# STM32G0B1CEU6.net
KiCad netlist of a schematic drawn in Altium Designer
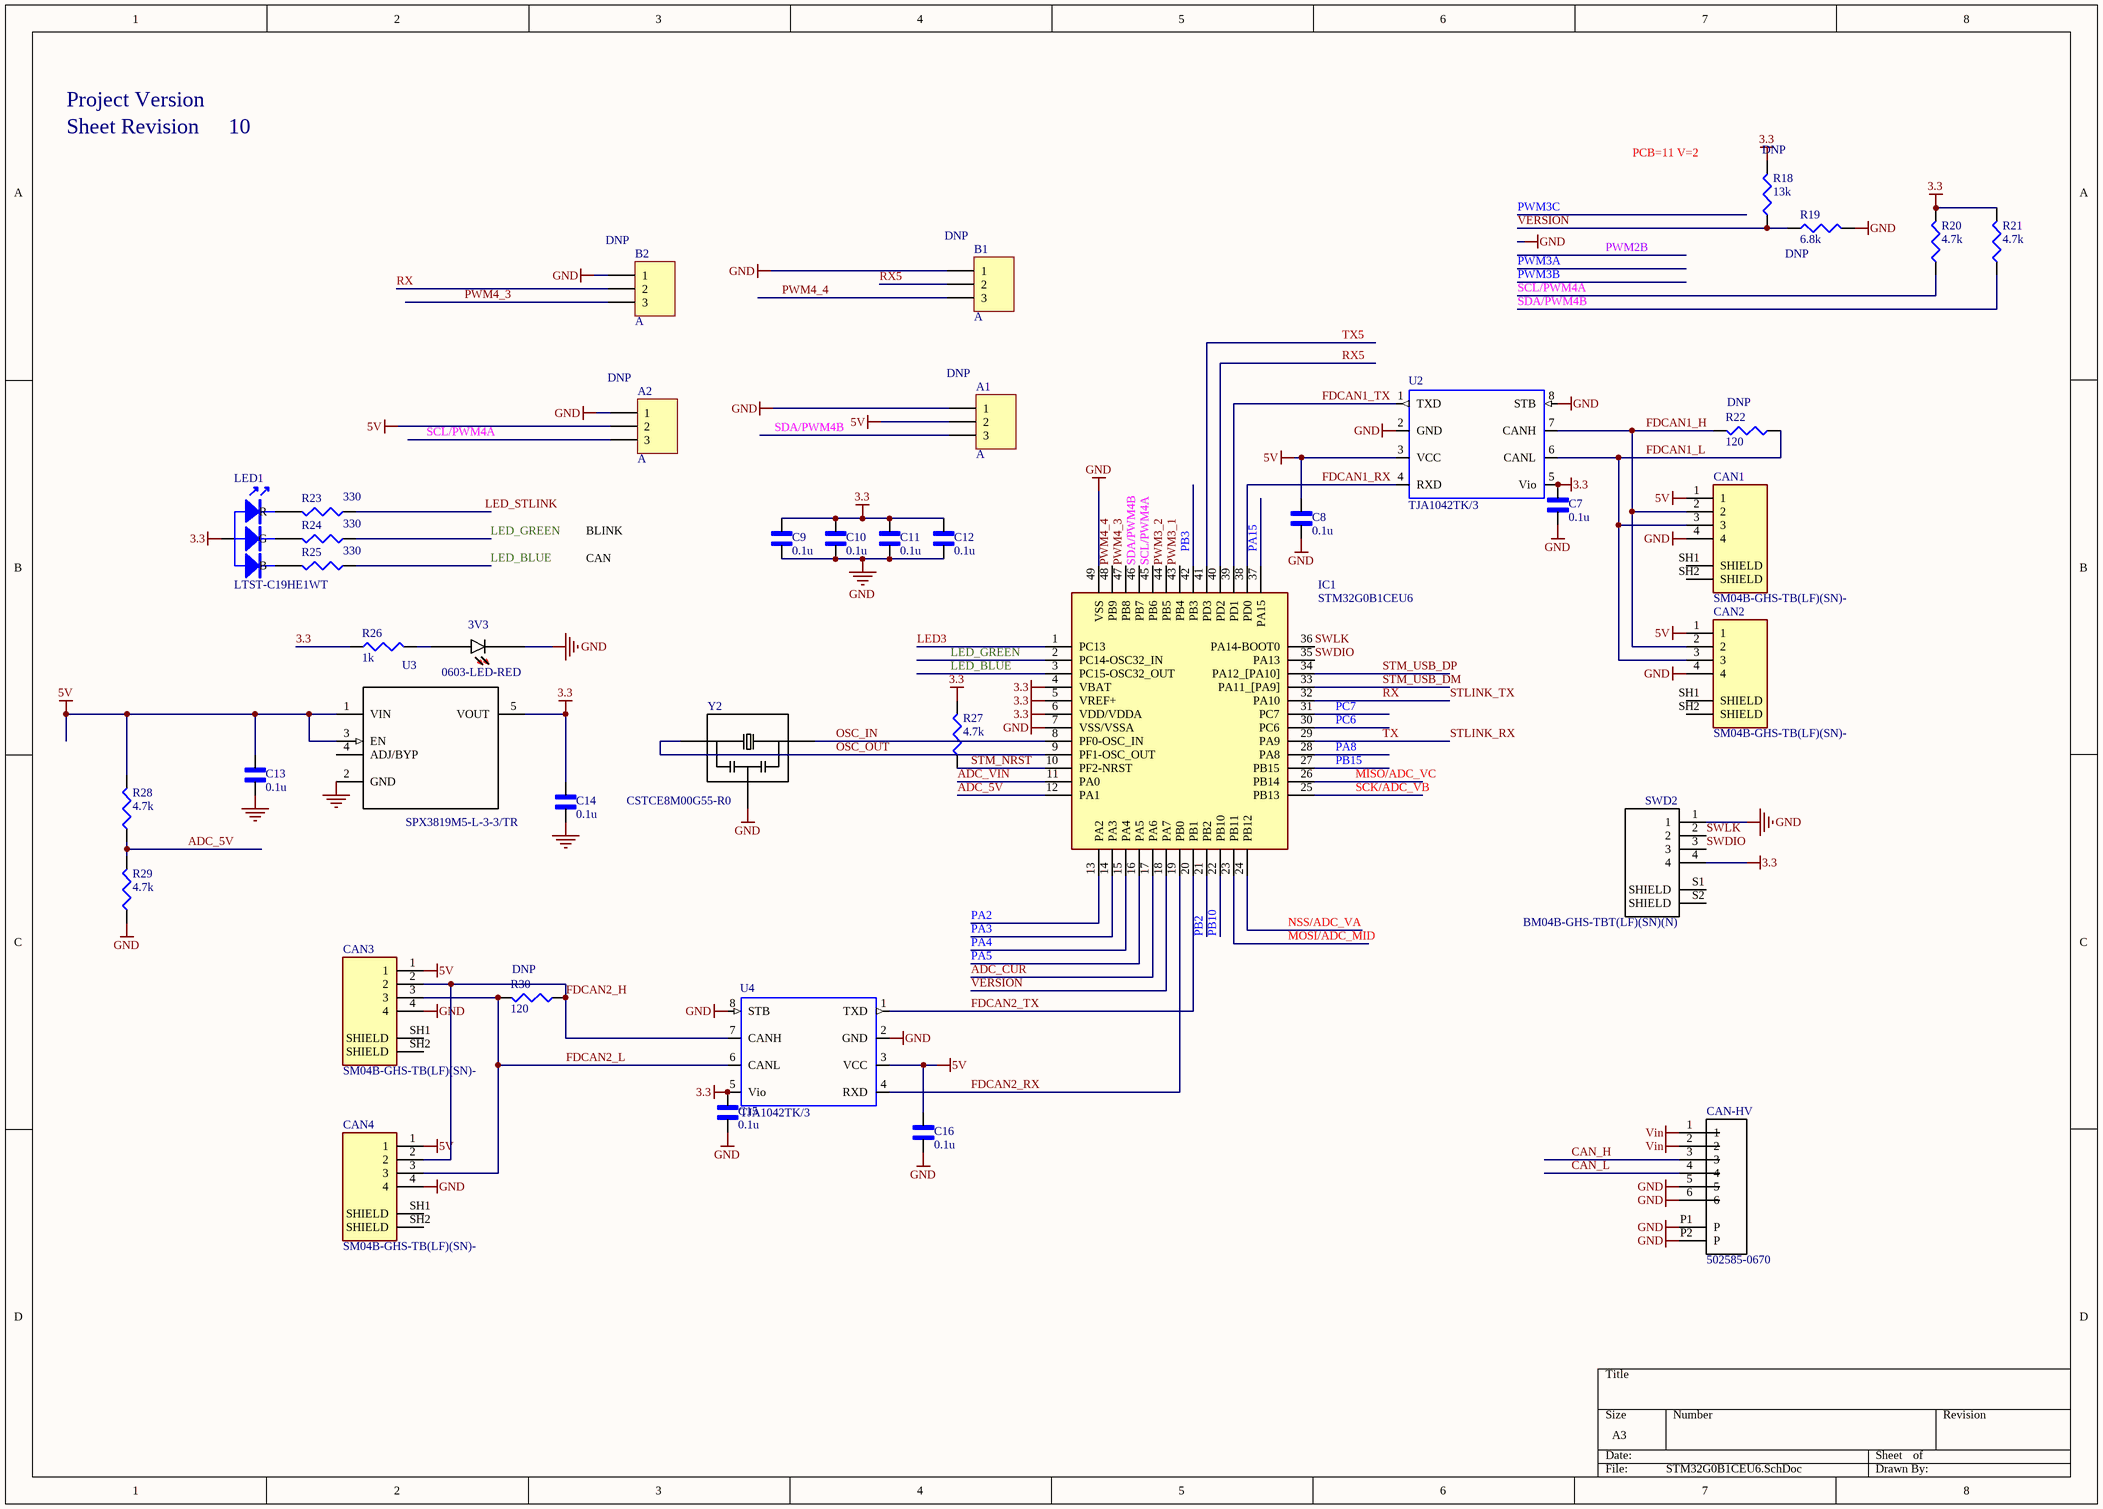
[diagram p0: STM32G0B1CEU6.SchDoc]

(export (version "E")
  (design (tool "Eeschema 10.0.6"))
  (components
    (comp (ref "3V3")
      (value "0603-LED-RED")
      (footprint "*LEDM1608X80_LTE-C1906R-14(Primary)")
      (description "Red 620nm LED Indication - Discrete 2.2V 0603 (1608 Metric)")
      (fields (field (name "MP") "LTST-C194KRKT"))
      (libsource (lib "lib") (part "0603-LED-RED"))
    )
    (comp (ref "A1")
      (value "A")
      (footprint "HDR Side 3 pin")
      (description "Header, 3-Pin")
      (fields
        (field (name "INSTRUCTIONS") "DNP")
        (field (name "MF") "Connfly electronic (Zhenqin)")
        (field (name "MP") "PLS-3 (DS1021-1x3)")
      )
      (libsource (lib "DC_DC") (part "Header 3"))
    )
    (comp (ref "A2")
      (value "A")
      (footprint "HDR Side 3 pin")
      (description "Header, 3-Pin")
      (fields
        (field (name "INSTRUCTIONS") "DNP")
        (field (name "MF") "Connfly electronic (Zhenqin)")
        (field (name "MP") "PLS-3 (DS1021-1x3)")
      )
      (libsource (lib "DC_DC") (part "Header 3"))
    )
    (comp (ref "B1")
      (value "A")
      (footprint "HDR Side 3 pin")
      (description "Header, 3-Pin")
      (fields
        (field (name "INSTRUCTIONS") "DNP")
        (field (name "MF") "Connfly electronic (Zhenqin)")
        (field (name "MP") "PLS-3 (DS1021-1x3)")
      )
      (libsource (lib "DC_DC") (part "Header 3"))
    )
    (comp (ref "B2")
      (value "A")
      (footprint "HDR Side 3 pin")
      (description "Header, 3-Pin")
      (fields
        (field (name "INSTRUCTIONS") "DNP")
        (field (name "MF") "Connfly electronic (Zhenqin)")
        (field (name "MP") "PLS-3 (DS1021-1x3)")
      )
      (libsource (lib "DC_DC") (part "Header 3"))
    )
    (comp (ref "C7")
      (value "0.1u")
      (footprint "CAPC1005X55N")
      (description "GCM155R71H104KE02D, Чип 0402 X7R 0.1uF +10% 50V,Конденсатор")
      (fields (field (name "MF") "Murata") (field (name "MP") "GCM155R71H104KE02D"))
      (libsource (lib "lib") (part "GCM155R71H104KE02D"))
    )
    (comp (ref "C8")
      (value "0.1u")
      (footprint "CAPC1005X55N")
      (description "GCM155R71H104KE02D, Чип 0402 X7R 0.1uF +10% 50V,Конденсатор")
      (fields (field (name "MF") "Murata") (field (name "MP") "GCM155R71H104KE02D"))
      (libsource (lib "lib") (part "GCM155R71H104KE02D"))
    )
    (comp (ref "C9")
      (value "0.1u")
      (footprint "CAPC1005X55N")
      (description "GCM155R71H104KE02D, Чип 0402 X7R 0.1uF +10% 50V,Конденсатор")
      (fields (field (name "MF") "Murata") (field (name "MP") "GCM155R71H104KE02D"))
      (libsource (lib "lib") (part "GCM155R71H104KE02D"))
    )
    (comp (ref "C10")
      (value "0.1u")
      (footprint "CAPC1005X55N")
      (description "GCM155R71H104KE02D, Чип 0402 X7R 0.1uF +10% 50V,Конденсатор")
      (fields (field (name "MF") "Murata") (field (name "MP") "GCM155R71H104KE02D"))
      (libsource (lib "lib") (part "GCM155R71H104KE02D"))
    )
    (comp (ref "C11")
      (value "0.1u")
      (footprint "CAPC1005X55N")
      (description "GCM155R71H104KE02D, Чип 0402 X7R 0.1uF +10% 50V,Конденсатор")
      (fields (field (name "MF") "Murata") (field (name "MP") "GCM155R71H104KE02D"))
      (libsource (lib "lib") (part "GCM155R71H104KE02D"))
    )
    (comp (ref "C12")
      (value "0.1u")
      (footprint "CAPC1005X55N")
      (description "GCM155R71H104KE02D, Чип 0402 X7R 0.1uF +10% 50V,Конденсатор")
      (fields (field (name "MF") "Murata") (field (name "MP") "GCM155R71H104KE02D"))
      (libsource (lib "lib") (part "GCM155R71H104KE02D"))
    )
    (comp (ref "C13")
      (value "0.1u")
      (footprint "CAPC1005X55N")
      (description "GCM155R71H104KE02D, Чип 0402 X7R 0.1uF +10% 50V,Конденсатор")
      (fields (field (name "MF") "Murata") (field (name "MP") "GCM155R71H104KE02D"))
      (libsource (lib "lib") (part "GCM155R71H104KE02D"))
    )
    (comp (ref "C14")
      (value "0.1u")
      (footprint "CAPC1005X55N")
      (description "GCM155R71H104KE02D, Чип 0402 X7R 0.1uF +10% 50V,Конденсатор")
      (fields (field (name "MF") "Murata") (field (name "MP") "GCM155R71H104KE02D"))
      (libsource (lib "lib") (part "GCM155R71H104KE02D"))
    )
    (comp (ref "C15")
      (value "0.1u")
      (footprint "CAPC1005X55N")
      (description "GCM155R71H104KE02D, Чип 0402 X7R 0.1uF +10% 50V,Конденсатор")
      (fields (field (name "MF") "Murata") (field (name "MP") "GCM155R71H104KE02D"))
      (libsource (lib "lib") (part "GCM155R71H104KE02D"))
    )
    (comp (ref "C16")
      (value "0.1u")
      (footprint "CAPC1005X55N")
      (description "GCM155R71H104KE02D, Чип 0402 X7R 0.1uF +10% 50V,Конденсатор")
      (fields (field (name "MF") "Murata") (field (name "MP") "GCM155R71H104KE02D"))
      (libsource (lib "lib") (part "GCM155R71H104KE02D"))
    )
    (comp (ref "CAN-HV")
      (value "502585-0670")
      (footprint "MOLEX_502585-0670")
      (fields (field (name "MF") "Molex"))
      (libsource (lib "lib") (part "502585-0670"))
    )
    (comp (ref "CAN1")
      (value "SM04B-GHS-TB(LF)(SN)-")
      (footprint "JST_SM04B-GHS-TB(LF)(SN)-")
      (description "Connector Header Surface Mount, Right Angle 4 position 0.049 _1.25mm_")
      (fields (field (name "MP") "SM04B-GHS-TB(LF)(SN)") (field (name "MF") "JST Sales"))
      (libsource (lib "") (part "SM04B-GHS-TB(LF)(SN)-_1"))
    )
    (comp (ref "CAN2")
      (value "SM04B-GHS-TB(LF)(SN)-")
      (footprint "JST_SM04B-GHS-TB(LF)(SN)-")
      (description "Connector Header Surface Mount, Right Angle 4 position 0.049 _1.25mm_")
      (fields (field (name "MP") "SM04B-GHS-TB(LF)(SN)") (field (name "MF") "JST Sales"))
      (libsource (lib "") (part "SM04B-GHS-TB(LF)(SN)-_1"))
    )
    (comp (ref "CAN3")
      (value "SM04B-GHS-TB(LF)(SN)-")
      (footprint "JST_SM04B-GHS-TB(LF)(SN)-")
      (description "Connector Header Surface Mount, Right Angle 4 position 0.049 _1.25mm_")
      (fields (field (name "MP") "SM04B-GHS-TB(LF)(SN)") (field (name "MF") "JST Sales"))
      (libsource (lib "lib") (part "SM04B-GHS-TB(LF)(SN)-"))
    )
    (comp (ref "CAN4")
      (value "SM04B-GHS-TB(LF)(SN)-")
      (footprint "JST_SM04B-GHS-TB(LF)(SN)-")
      (description "Connector Header Surface Mount, Right Angle 4 position 0.049 _1.25mm_")
      (fields (field (name "MP") "SM04B-GHS-TB(LF)(SN)") (field (name "MF") "JST Sales"))
      (libsource (lib "lib") (part "SM04B-GHS-TB(LF)(SN)-"))
    )
    (comp (ref "IC1")
      (value "STM32G0B1CEU6")
      (footprint "QFN50P700X700X60-49N-D")
      (description "Integrated Circuit")
      (fields
        (field (name "MF") "STMicroelectronics")
        (field (name "MOUSER PART NUMBER") "511-STM32G0B1CEU6")
      )
      (libsource (lib "lib") (part "STM32G0B1CxU6"))
    )
    (comp (ref "LED1")
      (value "LTST-C19HE1WT")
      (footprint "LTST-C19HE1WT")
      (description "Blue/Green/Red")
      (libsource (lib "lib") (part "RGB_LED_5MM"))
    )
    (comp (ref "R18")
      (value "13k")
      (footprint "RESC1005X40N")
      (description "0.062Вт 0402 13 кОм, 1%, Чип резистор (SMD)")
      (fields
        (field (name "INSTRUCTIONS") "DNP")
        (field (name "MF") "Yageo or NXP")
        (field (name "MP") "RC0402FR-0713KL")
      )
      (libsource (lib "lib") (part "RC0402FR-0713KL"))
    )
    (comp (ref "R19")
      (value "6.8k")
      (footprint "RESC1005X40N")
      (description "0.062Вт 0402 6.8 кОм, 1%, Чип резистор (SMD)")
      (fields
        (field (name "INSTRUCTIONS") "DNP")
        (field (name "MF") "Yageo or NXP")
        (field (name "MP") "RC0402FR-076K8L")
      )
      (libsource (lib "lib") (part "RC0402FR-076K8L"))
    )
    (comp (ref "R20")
      (value "4.7k")
      (footprint "RESC1005X40N")
      (description "0.062Вт 0402 4.7 кОм, 1%, Чип резистор (SMD)")
      (fields (field (name "MF") "Yageo or NXP") (field (name "MP") "RC0402FR-074K7L"))
      (libsource (lib "lib") (part "RC0402FR-074K7L"))
    )
    (comp (ref "R21")
      (value "4.7k")
      (footprint "RESC1005X40N")
      (description "0.062Вт 0402 4.7 кОм, 1%, Чип резистор (SMD)")
      (fields (field (name "MF") "Yageo or NXP") (field (name "MP") "RC0402FR-074K7L"))
      (libsource (lib "lib") (part "RC0402FR-074K7L"))
    )
    (comp (ref "R22")
      (value "120")
      (footprint "J1-0603")
      (description "120 Ohms 1 0.1 W 1 10 W Chip Resistor 0603 1608 Metric Thick Film")
      (fields
        (field (name "INSTRUCTIONS") "DNP")
        (field (name "MP") "RC0603FR-07120RL")
        (field (name "Comment") "Res3")
      )
      (libsource (lib "Miscellaneous Devices") (part "Res3"))
    )
    (comp (ref "R23")
      (value "330")
      (footprint "RESC1005X40N")
      (description "0.062Вт 0402 330 Ом, 1%, Чип резистор (SMD)")
      (fields (field (name "MF") "Yageo or NXP") (field (name "MP") "RC0402FR-07330RL"))
      (libsource (lib "lib") (part "RC0402FR-07330RL"))
    )
    (comp (ref "R24")
      (value "330")
      (footprint "RESC1005X40N")
      (description "0.062Вт 0402 330 Ом, 1%, Чип резистор (SMD)")
      (fields (field (name "MF") "Yageo or NXP") (field (name "MP") "RC0402FR-07330RL"))
      (libsource (lib "lib") (part "RC0402FR-07330RL"))
    )
    (comp (ref "R25")
      (value "330")
      (footprint "RESC1005X40N")
      (description "0.062Вт 0402 330 Ом, 1%, Чип резистор (SMD)")
      (fields (field (name "MF") "Yageo or NXP") (field (name "MP") "RC0402FR-07330RL"))
      (libsource (lib "lib") (part "RC0402FR-07330RL"))
    )
    (comp (ref "R26")
      (value "1k")
      (footprint "RESC1005X40N")
      (description "0.062Вт 0402 1 кОм, 1%, Чип резистор (SMD)")
      (fields (field (name "MF") "Yageo or NXP") (field (name "MP") "RC0402FR-071KL"))
      (libsource (lib "lib") (part "RC0402FR-071KL"))
    )
    (comp (ref "R27")
      (value "4.7k")
      (footprint "RESC1005X40N")
      (description "0.062Вт 0402 4.7 кОм, 1%, Чип резистор (SMD)")
      (fields (field (name "MF") "Yageo or NXP") (field (name "MP") "RC0402FR-074K7L"))
      (libsource (lib "lib") (part "RC0402FR-074K7L"))
    )
    (comp (ref "R28")
      (value "4.7k")
      (footprint "RESC1005X40N")
      (description "0.062Вт 0402 4.7 кОм, 1%, Чип резистор (SMD)")
      (fields (field (name "MF") "Yageo or NXP") (field (name "MP") "RC0402FR-074K7L"))
      (libsource (lib "lib") (part "RC0402FR-074K7L"))
    )
    (comp (ref "R29")
      (value "4.7k")
      (footprint "RESC1005X40N")
      (description "0.062Вт 0402 4.7 кОм, 1%, Чип резистор (SMD)")
      (fields (field (name "MF") "Yageo or NXP") (field (name "MP") "RC0402FR-074K7L"))
      (libsource (lib "lib") (part "RC0402FR-074K7L"))
    )
    (comp (ref "R30")
      (value "120")
      (footprint "J1-0603")
      (description "120 Ohms 1 0.1 W 1 10 W Chip Resistor 0603 1608 Metric Thick Film")
      (fields
        (field (name "INSTRUCTIONS") "DNP")
        (field (name "MP") "RC0603FR-07120RL")
        (field (name "Comment") "Res3")
      )
      (libsource (lib "Miscellaneous Devices") (part "Res3"))
    )
    (comp (ref "SWD2")
      (value "BM04B-GHS-TBT(LF)(SN)(N)")
      (footprint "JST_BM04B-GHS-holes")
      (description "Conn Shrouded Header HDR 4 POS 1.25mm Solder ST SMD Reel")
      (fields (field (name "MF") "JST Sales") (field (name "MP") "SM04B-GHS-TB(LF)(SN)"))
      (libsource (lib "lib") (part "BM04B-GHS-TBT(LF)(SN)(N)"))
    )
    (comp (ref "U2")
      (value "TJA1042TK/3")
      (footprint "SOT782-1")
      (description "1/1 Transceiver Half CANbus 8-SO")
      (fields (field (name "MF") "NXP USA"))
      (libsource (lib "lib") (part "TJA1042TK/3"))
    )
    (comp (ref "U3")
      (value "SPX3819M5-L-3-3/TR")
      (footprint "*SOT95P280X145-5N")
      (description "Low Dropout Voltage Regulator, Adjustable 0.5A, В±1%, 2.5 to 16 Vin, 5-Pin SOT-23")
      (fields (field (name "MF") "MaxLinear, Inc."))
      (libsource (lib "DC_DC") (part "SPX3819M5-L"))
    )
    (comp (ref "U4")
      (value "TJA1042TK/3")
      (footprint "SOT782-1")
      (description "1/1 Transceiver Half CANbus 8-SO")
      (fields (field (name "MF") "NXP USA"))
      (libsource (lib "lib") (part "TJA1042TK/3"))
    )
    (comp (ref "Y2")
      (value "CSTCE8M00G55-R0")
      (footprint "*OSC_CSTCE8M00G55-R0")
      (description "Ceramic Resonator 8MHz ??0.5% _Tol_ ??0.2% _Stability_ 33pF 40Ohm 3-Pin CSMD T/R")
      (fields (field (name "MP") "CSTCE8M00G55-R0 or CSTCE8M00G52-R0") (field (name "MF") "Murata"))
      (libsource (lib "lib") (part "CSTCE8M00G55-R0"))
    )
  )
  (nets
    (net (code "1") (name "/ADC_5V") (class "Default")
      (node (ref "IC1") (pin "12") (pinfunction "PA1_12") (pintype "passive"))
      (node (ref "R28") (pin "1") (pinfunction "1_1") (pintype "passive"))
      (node (ref "R29") (pin "2") (pinfunction "2_2") (pintype "passive"))
    )
    (net (code "2") (name "/ADC_CUR") (class "Default")
      (node (ref "IC1") (pin "17") (pinfunction "PA6_17") (pintype "passive"))
    )
    (net (code "3") (name "/ADC_VIN") (class "Default")
      (node (ref "IC1") (pin "11") (pinfunction "PA0_11") (pintype "passive"))
    )
    (net (code "4") (name "/CAN_H") (class "Default")
      (node (ref "CAN-HV") (pin "3") (pinfunction "3_3") (pintype "passive"))
    )
    (net (code "5") (name "/CAN_L") (class "Default")
      (node (ref "CAN-HV") (pin "4") (pinfunction "4_4") (pintype "passive"))
    )
    (net (code "6") (name "/FDCAN1_H") (class "Default")
      (node (ref "CAN1") (pin "2") (pinfunction "2_2") (pintype "passive"))
      (node (ref "CAN2") (pin "2") (pinfunction "2_2") (pintype "passive"))
      (node (ref "R22") (pin "2") (pinfunction "2_2") (pintype "passive"))
      (node (ref "U2") (pin "7") (pinfunction "CANH_7") (pintype "bidirectional"))
    )
    (net (code "7") (name "/FDCAN1_L") (class "Default")
      (node (ref "CAN1") (pin "3") (pinfunction "3_3") (pintype "passive"))
      (node (ref "CAN2") (pin "3") (pinfunction "3_3") (pintype "passive"))
      (node (ref "R22") (pin "1") (pinfunction "1_1") (pintype "passive"))
      (node (ref "U2") (pin "6") (pinfunction "CANL_6") (pintype "bidirectional"))
    )
    (net (code "8") (name "/FDCAN1_RX") (class "Default")
      (node (ref "IC1") (pin "38") (pinfunction "PD0_38") (pintype "passive"))
      (node (ref "U2") (pin "4") (pinfunction "RXD_4") (pintype "bidirectional"))
    )
    (net (code "9") (name "/FDCAN1_TX") (class "Default")
      (node (ref "IC1") (pin "39") (pinfunction "PD1_39") (pintype "passive"))
      (node (ref "U2") (pin "1") (pinfunction "TXD_1") (pintype "output"))
    )
    (net (code "10") (name "/FDCAN2_H") (class "Default")
      (node (ref "CAN3") (pin "2") (pinfunction "2_2") (pintype "passive"))
      (node (ref "CAN4") (pin "2") (pinfunction "2_2") (pintype "passive"))
      (node (ref "R30") (pin "1") (pinfunction "1_1") (pintype "passive"))
      (node (ref "U4") (pin "7") (pinfunction "CANH_7") (pintype "bidirectional"))
    )
    (net (code "11") (name "/FDCAN2_L") (class "Default")
      (node (ref "CAN3") (pin "3") (pinfunction "3_3") (pintype "passive"))
      (node (ref "CAN4") (pin "3") (pinfunction "3_3") (pintype "passive"))
      (node (ref "R30") (pin "2") (pinfunction "2_2") (pintype "passive"))
      (node (ref "U4") (pin "6") (pinfunction "CANL_6") (pintype "bidirectional"))
    )
    (net (code "12") (name "/FDCAN2_RX") (class "Default")
      (node (ref "IC1") (pin "19") (pinfunction "PB0_19") (pintype "passive"))
      (node (ref "U4") (pin "4") (pinfunction "RXD_4") (pintype "bidirectional"))
    )
    (net (code "13") (name "/FDCAN2_TX") (class "Default")
      (node (ref "IC1") (pin "20") (pinfunction "PB1_20") (pintype "passive"))
      (node (ref "U4") (pin "1") (pinfunction "TXD_1") (pintype "output"))
    )
    (net (code "14") (name "/LED3") (class "Default")
      (node (ref "IC1") (pin "1") (pinfunction "PC13_1") (pintype "passive"))
    )
    (net (code "15") (name "/LED_BLUE") (class "Default")
      (node (ref "IC1") (pin "3") (pinfunction "PC15-OSC32_OUT_3") (pintype "passive"))
      (node (ref "R25") (pin "1") (pinfunction "1_1") (pintype "passive"))
    )
    (net (code "16") (name "/LED_GREEN") (class "Default")
      (node (ref "IC1") (pin "2") (pinfunction "PC14-OSC32_IN_2") (pintype "passive"))
      (node (ref "R24") (pin "1") (pinfunction "1_1") (pintype "passive"))
    )
    (net (code "17") (name "/LED_STLINK") (class "Default")
      (node (ref "R23") (pin "1") (pinfunction "1_1") (pintype "passive"))
    )
    (net (code "18") (name "/MISO{slash}ADC_VC") (class "Default")
      (node (ref "IC1") (pin "26") (pinfunction "PB14_26") (pintype "passive"))
    )
    (net (code "19") (name "/MOSI{slash}ADC_MID") (class "Default")
      (node (ref "IC1") (pin "23") (pinfunction "PB11_23") (pintype "passive"))
    )
    (net (code "20") (name "/NSS{slash}ADC_VA") (class "Default")
      (node (ref "IC1") (pin "24") (pinfunction "PB12_24") (pintype "passive"))
    )
    (net (code "21") (name "/OSC_IN") (class "Default")
      (node (ref "IC1") (pin "8") (pinfunction "PF0-OSC_IN_8") (pintype "passive"))
      (node (ref "Y2") (pin "3") (pinfunction "3_3") (pintype "passive"))
    )
    (net (code "22") (name "/OSC_OUT") (class "Default")
      (node (ref "IC1") (pin "9") (pinfunction "PF1-OSC_OUT_9") (pintype "passive"))
      (node (ref "Y2") (pin "1") (pinfunction "1_1") (pintype "passive"))
    )
    (net (code "23") (name "/PA2") (class "Default")
      (node (ref "IC1") (pin "13") (pinfunction "PA2_13") (pintype "passive"))
    )
    (net (code "24") (name "/PA3") (class "Default")
      (node (ref "IC1") (pin "14") (pinfunction "PA3_14") (pintype "passive"))
    )
    (net (code "25") (name "/PA4") (class "Default")
      (node (ref "IC1") (pin "15") (pinfunction "PA4_15") (pintype "passive"))
    )
    (net (code "26") (name "/PA5") (class "Default")
      (node (ref "IC1") (pin "16") (pinfunction "PA5_16") (pintype "passive"))
    )
    (net (code "27") (name "/PA8") (class "Default")
      (node (ref "IC1") (pin "28") (pinfunction "PA8_28") (pintype "passive"))
    )
    (net (code "28") (name "/PA15") (class "Default")
      (node (ref "IC1") (pin "37") (pinfunction "PA15_37") (pintype "passive"))
    )
    (net (code "29") (name "/PB2") (class "Default")
      (node (ref "IC1") (pin "21") (pinfunction "PB2_21") (pintype "passive"))
    )
    (net (code "30") (name "/PB3") (class "Default")
      (node (ref "IC1") (pin "42") (pinfunction "PB3_42") (pintype "passive"))
    )
    (net (code "31") (name "/PB10") (class "Default")
      (node (ref "IC1") (pin "22") (pinfunction "PB10_22") (pintype "passive"))
    )
    (net (code "32") (name "/PB15") (class "Default")
      (node (ref "IC1") (pin "27") (pinfunction "PB15_27") (pintype "passive"))
    )
    (net (code "33") (name "/PC6") (class "Default")
      (node (ref "IC1") (pin "30") (pinfunction "PC6_30") (pintype "passive"))
    )
    (net (code "34") (name "/PC7") (class "Default")
      (node (ref "IC1") (pin "31") (pinfunction "PC7_31") (pintype "passive"))
    )
    (net (code "39") (name "/PWM3_1") (class "Default")
      (node (ref "IC1") (pin "43") (pinfunction "PB4_43") (pintype "passive"))
    )
    (net (code "40") (name "/PWM3_2") (class "Default")
      (node (ref "IC1") (pin "44") (pinfunction "PB5_44") (pintype "passive"))
    )
    (net (code "41") (name "/PWM4_3") (class "Default")
      (node (ref "B2") (pin "3") (pinfunction "3_3") (pintype "passive"))
      (node (ref "IC1") (pin "47") (pinfunction "PB8_47") (pintype "passive"))
    )
    (net (code "42") (name "/PWM4_4") (class "Default")
      (node (ref "B1") (pin "3") (pinfunction "3_3") (pintype "passive"))
      (node (ref "IC1") (pin "48") (pinfunction "PB9_48") (pintype "passive"))
    )
    (net (code "43") (name "/RX") (class "Default")
      (node (ref "B2") (pin "2") (pinfunction "2_2") (pintype "passive"))
      (node (ref "IC1") (pin "32") (pinfunction "PA10_32") (pintype "passive"))
    )
    (net (code "44") (name "/RX5") (class "Default")
      (node (ref "B1") (pin "2") (pinfunction "2_2") (pintype "passive"))
      (node (ref "IC1") (pin "40") (pinfunction "PD2_40") (pintype "passive"))
    )
    (net (code "45") (name "/SCK{slash}ADC_VB") (class "Default")
      (node (ref "IC1") (pin "25") (pinfunction "PB13_25") (pintype "passive"))
    )
    (net (code "46") (name "/SCL{slash}PWM4A") (class "Default")
      (node (ref "A2") (pin "3") (pinfunction "3_3") (pintype "passive"))
      (node (ref "IC1") (pin "45") (pinfunction "PB6_45") (pintype "passive"))
      (node (ref "R20") (pin "1") (pinfunction "1_1") (pintype "passive"))
    )
    (net (code "47") (name "/SDA{slash}PWM4B") (class "Default")
      (node (ref "A1") (pin "3") (pinfunction "3_3") (pintype "passive"))
      (node (ref "IC1") (pin "46") (pinfunction "PB7_46") (pintype "passive"))
      (node (ref "R21") (pin "1") (pinfunction "1_1") (pintype "passive"))
    )
    (net (code "48") (name "/STLINK_RX") (class "Default")
      (node (ref "IC1") (pin "29") (pinfunction "PA9_29") (pintype "passive"))
    )
    (net (code "49") (name "/STM_NRST") (class "Default")
      (node (ref "IC1") (pin "10") (pinfunction "PF2-NRST_10") (pintype "passive"))
      (node (ref "R27") (pin "1") (pinfunction "1_1") (pintype "passive"))
    )
    (net (code "50") (name "/STM_USB_DM") (class "Default")
      (node (ref "IC1") (pin "33") (pinfunction "PA11_[PA9]_33") (pintype "passive"))
    )
    (net (code "51") (name "/STM_USB_DP") (class "Default")
      (node (ref "IC1") (pin "34") (pinfunction "PA12_[PA10]_34") (pintype "passive"))
    )
    (net (code "52") (name "/SWDIO") (class "Default")
      (node (ref "IC1") (pin "35") (pinfunction "PA13_35") (pintype "passive"))
      (node (ref "SWD2") (pin "3") (pinfunction "3_3") (pintype "passive"))
    )
    (net (code "53") (name "/SWLK") (class "Default")
      (node (ref "IC1") (pin "36") (pinfunction "PA14-BOOT0_36") (pintype "passive"))
      (node (ref "SWD2") (pin "2") (pinfunction "2_2") (pintype "passive"))
    )
    (net (code "54") (name "/TX5") (class "Default")
      (node (ref "IC1") (pin "41") (pinfunction "PD3_41") (pintype "passive"))
    )
    (net (code "55") (name "/VERSION") (class "Default")
      (node (ref "IC1") (pin "18") (pinfunction "PA7_18") (pintype "passive"))
      (node (ref "R18") (pin "1") (pinfunction "1_1") (pintype "passive"))
      (node (ref "R19") (pin "1") (pinfunction "1_1") (pintype "passive"))
    )
    (net (code "56") (name "3.3") (class "Default")
      (node (ref "C10") (pin "2") (pinfunction "2_2") (pintype "passive"))
      (node (ref "C11") (pin "2") (pinfunction "2_2") (pintype "passive"))
      (node (ref "C12") (pin "2") (pinfunction "2_2") (pintype "passive"))
      (node (ref "C14") (pin "2") (pinfunction "2_2") (pintype "passive"))
      (node (ref "C15") (pin "2") (pinfunction "2_2") (pintype "passive"))
      (node (ref "C7") (pin "2") (pinfunction "2_2") (pintype "passive"))
      (node (ref "C9") (pin "2") (pinfunction "2_2") (pintype "passive"))
      (node (ref "IC1") (pin "4") (pinfunction "VBAT_4") (pintype "passive"))
      (node (ref "IC1") (pin "5") (pinfunction "VREF+_5") (pintype "passive"))
      (node (ref "IC1") (pin "6") (pinfunction "VDD/VDDA_6") (pintype "passive"))
      (node (ref "LED1") (pin "4") (pinfunction "A_4") (pintype "passive"))
      (node (ref "R18") (pin "2") (pinfunction "2_2") (pintype "passive"))
      (node (ref "R20") (pin "2") (pinfunction "2_2") (pintype "passive"))
      (node (ref "R21") (pin "2") (pinfunction "2_2") (pintype "passive"))
      (node (ref "R26") (pin "1") (pinfunction "1_1") (pintype "passive"))
      (node (ref "R27") (pin "2") (pinfunction "2_2") (pintype "passive"))
      (node (ref "SWD2") (pin "4") (pinfunction "4_4") (pintype "passive"))
      (node (ref "U2") (pin "5") (pinfunction "Vio_5") (pintype "power_in"))
      (node (ref "U3") (pin "5") (pinfunction "VOUT_5") (pintype "power_in"))
      (node (ref "U4") (pin "5") (pinfunction "Vio_5") (pintype "power_in"))
    )
    (net (code "57") (name "5V") (class "Default")
      (node (ref "A1") (pin "2") (pinfunction "2_2") (pintype "passive"))
      (node (ref "A2") (pin "2") (pinfunction "2_2") (pintype "passive"))
      (node (ref "C13") (pin "2") (pinfunction "2_2") (pintype "passive"))
      (node (ref "C16") (pin "2") (pinfunction "2_2") (pintype "passive"))
      (node (ref "C8") (pin "2") (pinfunction "2_2") (pintype "passive"))
      (node (ref "CAN1") (pin "1") (pinfunction "1_1") (pintype "passive"))
      (node (ref "CAN2") (pin "1") (pinfunction "1_1") (pintype "passive"))
      (node (ref "CAN3") (pin "1") (pinfunction "1_1") (pintype "passive"))
      (node (ref "CAN4") (pin "1") (pinfunction "1_1") (pintype "passive"))
      (node (ref "R28") (pin "2") (pinfunction "2_2") (pintype "passive"))
      (node (ref "U2") (pin "3") (pinfunction "VCC_3") (pintype "power_in"))
      (node (ref "U3") (pin "1") (pinfunction "VIN_1") (pintype "power_in"))
      (node (ref "U3") (pin "3") (pinfunction "EN_3") (pintype "input"))
      (node (ref "U4") (pin "3") (pinfunction "VCC_3") (pintype "power_in"))
    )
    (net (code "58") (name "GND") (class "Default")
      (node (ref "3V3") (pin "C") (pinfunction "C_C") (pintype "passive"))
      (node (ref "A1") (pin "1") (pinfunction "1_1") (pintype "passive"))
      (node (ref "A2") (pin "1") (pinfunction "1_1") (pintype "passive"))
      (node (ref "B1") (pin "1") (pinfunction "1_1") (pintype "passive"))
      (node (ref "B2") (pin "1") (pinfunction "1_1") (pintype "passive"))
      (node (ref "C10") (pin "1") (pinfunction "1_1") (pintype "passive"))
      (node (ref "C11") (pin "1") (pinfunction "1_1") (pintype "passive"))
      (node (ref "C12") (pin "1") (pinfunction "1_1") (pintype "passive"))
      (node (ref "C13") (pin "1") (pinfunction "1_1") (pintype "passive"))
      (node (ref "C14") (pin "1") (pinfunction "1_1") (pintype "passive"))
      (node (ref "C15") (pin "1") (pinfunction "1_1") (pintype "passive"))
      (node (ref "C16") (pin "1") (pinfunction "1_1") (pintype "passive"))
      (node (ref "C7") (pin "1") (pinfunction "1_1") (pintype "passive"))
      (node (ref "C8") (pin "1") (pinfunction "1_1") (pintype "passive"))
      (node (ref "C9") (pin "1") (pinfunction "1_1") (pintype "passive"))
      (node (ref "CAN-HV") (pin "5") (pinfunction "5_5") (pintype "passive"))
      (node (ref "CAN-HV") (pin "6") (pinfunction "6_6") (pintype "passive"))
      (node (ref "CAN-HV") (pin "P1") (pinfunction "P_P1") (pintype "passive"))
      (node (ref "CAN-HV") (pin "P2") (pinfunction "P_P2") (pintype "passive"))
      (node (ref "CAN1") (pin "4") (pinfunction "4_4") (pintype "passive"))
      (node (ref "CAN2") (pin "4") (pinfunction "4_4") (pintype "passive"))
      (node (ref "CAN3") (pin "4") (pinfunction "4_4") (pintype "passive"))
      (node (ref "CAN4") (pin "4") (pinfunction "4_4") (pintype "passive"))
      (node (ref "IC1") (pin "49") (pinfunction "VSS_49") (pintype "passive"))
      (node (ref "IC1") (pin "7") (pinfunction "VSS/VSSA_7") (pintype "passive"))
      (node (ref "R19") (pin "2") (pinfunction "2_2") (pintype "passive"))
      (node (ref "R29") (pin "1") (pinfunction "1_1") (pintype "passive"))
      (node (ref "SWD2") (pin "1") (pinfunction "1_1") (pintype "passive"))
      (node (ref "U2") (pin "2") (pinfunction "GND_2") (pintype "power_in"))
      (node (ref "U2") (pin "8") (pinfunction "STB_8") (pintype "input"))
      (node (ref "U3") (pin "2") (pinfunction "GND_2") (pintype "passive"))
      (node (ref "U4") (pin "2") (pinfunction "GND_2") (pintype "power_in"))
      (node (ref "U4") (pin "8") (pinfunction "STB_8") (pintype "input"))
      (node (ref "Y2") (pin "2") (pinfunction "2_2") (pintype "power_in"))
    )
    (net (code "59") (name "Net-(3V3-PadA)") (class "Default")
      (node (ref "3V3") (pin "A") (pinfunction "A_A") (pintype "passive"))
      (node (ref "R26") (pin "2") (pinfunction "2_2") (pintype "passive"))
    )
    (net (code "60") (name "Net-(LED1-B)") (class "Default")
      (node (ref "LED1") (pin "3") (pinfunction "B_3") (pintype "passive"))
      (node (ref "R25") (pin "2") (pinfunction "2_2") (pintype "passive"))
    )
    (net (code "61") (name "Net-(LED1-G)") (class "Default")
      (node (ref "LED1") (pin "2") (pinfunction "G_2") (pintype "passive"))
      (node (ref "R24") (pin "2") (pinfunction "2_2") (pintype "passive"))
    )
    (net (code "62") (name "Net-(LED1-R)") (class "Default")
      (node (ref "LED1") (pin "1") (pinfunction "R_1") (pintype "passive"))
      (node (ref "R23") (pin "2") (pinfunction "2_2") (pintype "passive"))
    )
    (net (code "63") (name "Vin") (class "Default")
      (node (ref "CAN-HV") (pin "1") (pinfunction "1_1") (pintype "passive"))
      (node (ref "CAN-HV") (pin "2") (pinfunction "2_2") (pintype "passive"))
    )
    (net (code "64") (name "unconnected-(CAN1-SHIELD-PadSH1)") (class "Default")
      (node (ref "CAN1") (pin "SH1") (pinfunction "SHIELD_SH1") (pintype "power_in"))
    )
    (net (code "65") (name "unconnected-(CAN1-SHIELD-PadSH2)") (class "Default")
      (node (ref "CAN1") (pin "SH2") (pinfunction "SHIELD_SH2") (pintype "power_in"))
    )
    (net (code "66") (name "unconnected-(CAN2-SHIELD-PadSH1)") (class "Default")
      (node (ref "CAN2") (pin "SH1") (pinfunction "SHIELD_SH1") (pintype "power_in"))
    )
    (net (code "67") (name "unconnected-(CAN2-SHIELD-PadSH2)") (class "Default")
      (node (ref "CAN2") (pin "SH2") (pinfunction "SHIELD_SH2") (pintype "power_in"))
    )
    (net (code "68") (name "unconnected-(CAN3-SHIELD-PadSH1)") (class "Default")
      (node (ref "CAN3") (pin "SH1") (pinfunction "SHIELD_SH1") (pintype "power_in"))
    )
    (net (code "69") (name "unconnected-(CAN3-SHIELD-PadSH2)") (class "Default")
      (node (ref "CAN3") (pin "SH2") (pinfunction "SHIELD_SH2") (pintype "power_in"))
    )
    (net (code "70") (name "unconnected-(CAN4-SHIELD-PadSH1)") (class "Default")
      (node (ref "CAN4") (pin "SH1") (pinfunction "SHIELD_SH1") (pintype "power_in"))
    )
    (net (code "71") (name "unconnected-(CAN4-SHIELD-PadSH2)") (class "Default")
      (node (ref "CAN4") (pin "SH2") (pinfunction "SHIELD_SH2") (pintype "power_in"))
    )
    (net (code "72") (name "unconnected-(SWD2-SHIELD-PadS1)") (class "Default")
      (node (ref "SWD2") (pin "S1") (pinfunction "SHIELD_S1") (pintype "passive"))
    )
    (net (code "73") (name "unconnected-(SWD2-SHIELD-PadS2)") (class "Default")
      (node (ref "SWD2") (pin "S2") (pinfunction "SHIELD_S2") (pintype "passive"))
    )
    (net (code "74") (name "unconnected-(U3-ADJ{slash}BYP-Pad4)") (class "Default")
      (node (ref "U3") (pin "4") (pinfunction "ADJ/BYP_4") (pintype "passive"))
    )
  )
)
